# PIZ-Dual_v886.net
KiCad netlist of a schematic drawn in EAGLE
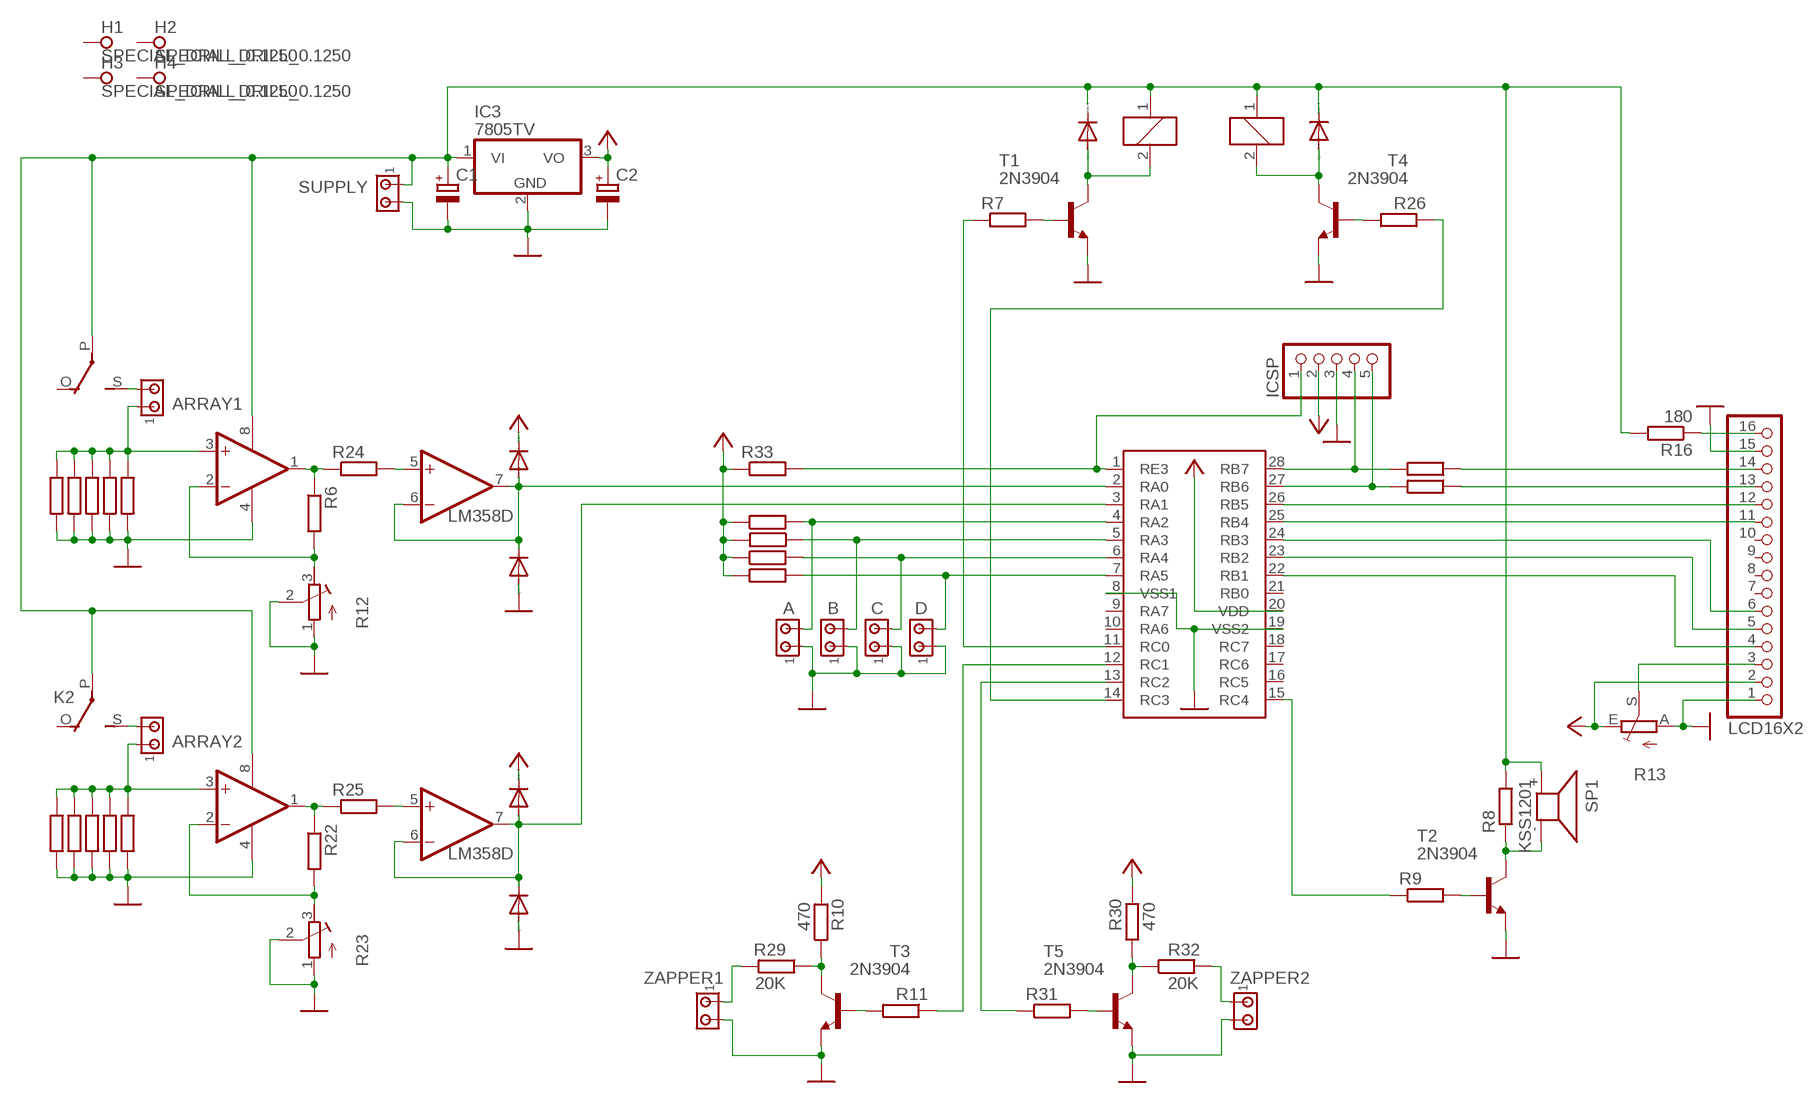
[diagram p0: schematic, sheet 1]

(export (version "E")
  (design (tool "Eeschema 10.0.6"))
  (components
    (comp (ref "A")
      (value "MTA02-100")
      (footprint "eagle-import:10X02MTA")
      (libsource (lib "eagle-import") (part "MTA02-100"))
    )
    (comp (ref "ARRAY1")
      (value "MTA02-100")
      (footprint "eagle-import:10X02MTA")
      (libsource (lib "eagle-import") (part "MTA02-100"))
    )
    (comp (ref "ARRAY2")
      (value "MTA02-100")
      (footprint "eagle-import:10X02MTA")
      (libsource (lib "eagle-import") (part "MTA02-100"))
    )
    (comp (ref "B")
      (value "MTA02-100")
      (footprint "eagle-import:10X02MTA")
      (libsource (lib "eagle-import") (part "MTA02-100"))
    )
    (comp (ref "C")
      (value "MTA02-100")
      (footprint "eagle-import:10X02MTA")
      (libsource (lib "eagle-import") (part "MTA02-100"))
    )
    (comp (ref "C1")
      (value "CPOL-EUE2.5-7")
      (footprint "eagle-import:E2,5-7")
      (libsource (lib "eagle-import") (part "CPOL-EUE2.5-7"))
    )
    (comp (ref "C2")
      (value "CPOL-EUE2.5-7")
      (footprint "eagle-import:E2,5-7")
      (libsource (lib "eagle-import") (part "CPOL-EUE2.5-7"))
    )
    (comp (ref "D")
      (value "MTA02-100")
      (footprint "eagle-import:10X02MTA")
      (libsource (lib "eagle-import") (part "MTA02-100"))
    )
    (comp (ref "D1")
      (value "1N4148DO35-7")
      (footprint "eagle-import:DO35-7")
      (libsource (lib "eagle-import") (part "1N4148DO35-7"))
    )
    (comp (ref "D2")
      (value "1N4148DO35-7")
      (footprint "eagle-import:DO35-7")
      (libsource (lib "eagle-import") (part "1N4148DO35-7"))
    )
    (comp (ref "D3")
      (value "1N4148DO35-7")
      (footprint "eagle-import:DO35-7")
      (libsource (lib "eagle-import") (part "1N4148DO35-7"))
    )
    (comp (ref "D4")
      (value "1N4148DO35-7")
      (footprint "eagle-import:DO35-7")
      (libsource (lib "eagle-import") (part "1N4148DO35-7"))
    )
    (comp (ref "D5")
      (value "1N4148DO35-7")
      (footprint "eagle-import:DO35-7")
      (libsource (lib "eagle-import") (part "1N4148DO35-7"))
    )
    (comp (ref "D6")
      (value "1N4148DO35-7")
      (footprint "eagle-import:DO35-7")
      (libsource (lib "eagle-import") (part "1N4148DO35-7"))
    )
    (comp (ref "H1")
      (value "SPECIAL_DRILL_0.1250")
      (footprint "eagle-import:PAD_0.1250")
      (libsource (lib "eagle-import") (part "SPECIAL_DRILL_0.1250"))
    )
    (comp (ref "H2")
      (value "SPECIAL_DRILL_0.1250")
      (footprint "eagle-import:PAD_0.1250")
      (libsource (lib "eagle-import") (part "SPECIAL_DRILL_0.1250"))
    )
    (comp (ref "H3")
      (value "SPECIAL_DRILL_0.1250")
      (footprint "eagle-import:PAD_0.1250")
      (libsource (lib "eagle-import") (part "SPECIAL_DRILL_0.1250"))
    )
    (comp (ref "H4")
      (value "SPECIAL_DRILL_0.1250")
      (footprint "eagle-import:PAD_0.1250")
      (libsource (lib "eagle-import") (part "SPECIAL_DRILL_0.1250"))
    )
    (comp (ref "IC2")
      (value "LM358D")
      (footprint "eagle-import:SO08")
      (libsource (lib "eagle-import") (part "LM358D"))
    )
    (comp (ref "IC3")
      (value "7805TV")
      (footprint "eagle-import:TO220V")
      (libsource (lib "eagle-import") (part "78TV05"))
    )
    (comp (ref "IC4")
      (value "LM358D")
      (footprint "eagle-import:SO08")
      (libsource (lib "eagle-import") (part "LM358D"))
    )
    (comp (ref "ICSP")
      (value "PINHD-1X55X2MM")
      (footprint "eagle-import:1_05X2MM")
      (libsource (lib "eagle-import") (part "PINHD-1X55X2MM"))
    )
    (comp (ref "K1")
      (value "G5L")
      (footprint "eagle-import:G5LE")
      (libsource (lib "eagle-import") (part "G5L"))
    )
    (comp (ref "K2")
      (value "G5L")
      (footprint "eagle-import:G5LE")
      (libsource (lib "eagle-import") (part "G5L"))
    )
    (comp (ref "LCD16X2")
      (value "PINHD-1X16")
      (footprint "eagle-import:1X16")
      (libsource (lib "eagle-import") (part "PINHD-1X16"))
    )
    (comp (ref "R1")
      (value "R-EU_R1210")
      (footprint "eagle-import:R1210")
      (libsource (lib "eagle-import") (part "R-EU_R1210"))
    )
    (comp (ref "R2")
      (value "R-EU_R1210")
      (footprint "eagle-import:R1210")
      (libsource (lib "eagle-import") (part "R-EU_R1210"))
    )
    (comp (ref "R3")
      (value "R-EU_R1210")
      (footprint "eagle-import:R1210")
      (libsource (lib "eagle-import") (part "R-EU_R1210"))
    )
    (comp (ref "R4")
      (value "R-EU_R1210")
      (footprint "eagle-import:R1210")
      (libsource (lib "eagle-import") (part "R-EU_R1210"))
    )
    (comp (ref "R5")
      (value "R-EU_R1210")
      (footprint "eagle-import:R1210")
      (libsource (lib "eagle-import") (part "R-EU_R1210"))
    )
    (comp (ref "R6")
      (value "R-EU_R1206")
      (footprint "eagle-import:R1206")
      (libsource (lib "eagle-import") (part "R-EU_R1206"))
    )
    (comp (ref "R7")
      (value "R-EU_R1206")
      (footprint "eagle-import:R1206")
      (libsource (lib "eagle-import") (part "R-EU_R1206"))
    )
    (comp (ref "R8")
      (value "R-EU_R1210")
      (footprint "eagle-import:R1210")
      (libsource (lib "eagle-import") (part "R-EU_R1210"))
    )
    (comp (ref "R9")
      (value "R-EU_R1206")
      (footprint "eagle-import:R1206")
      (libsource (lib "eagle-import") (part "R-EU_R1206"))
    )
    (comp (ref "R10")
      (value "470")
      (footprint "eagle-import:R1206")
      (libsource (lib "eagle-import") (part "R-EU_R1206"))
    )
    (comp (ref "R11")
      (value "R-EU_R1206")
      (footprint "eagle-import:R1206")
      (libsource (lib "eagle-import") (part "R-EU_R1206"))
    )
    (comp (ref "R12")
      (value "R-TRIMM64W")
      (footprint "eagle-import:RTRIM64W")
      (libsource (lib "eagle-import") (part "R-TRIMM64W"))
    )
    (comp (ref "R13")
      (value "TRIM_EU-CA6V")
      (footprint "eagle-import:CA6V")
      (libsource (lib "eagle-import") (part "TRIM_EU-CA6V"))
    )
    (comp (ref "R14")
      (value "R-EU_R1206")
      (footprint "eagle-import:R1206")
      (libsource (lib "eagle-import") (part "R-EU_R1206"))
    )
    (comp (ref "R15")
      (value "R-EU_R1206")
      (footprint "eagle-import:R1206")
      (libsource (lib "eagle-import") (part "R-EU_R1206"))
    )
    (comp (ref "R16")
      (value "180")
      (footprint "eagle-import:R2512")
      (libsource (lib "eagle-import") (part "R-EU_R2512"))
    )
    (comp (ref "R17")
      (value "R-EU_R1210")
      (footprint "eagle-import:R1210")
      (libsource (lib "eagle-import") (part "R-EU_R1210"))
    )
    (comp (ref "R18")
      (value "R-EU_R1210")
      (footprint "eagle-import:R1210")
      (libsource (lib "eagle-import") (part "R-EU_R1210"))
    )
    (comp (ref "R19")
      (value "R-EU_R1210")
      (footprint "eagle-import:R1210")
      (libsource (lib "eagle-import") (part "R-EU_R1210"))
    )
    (comp (ref "R20")
      (value "R-EU_R1210")
      (footprint "eagle-import:R1210")
      (libsource (lib "eagle-import") (part "R-EU_R1210"))
    )
    (comp (ref "R21")
      (value "R-EU_R1210")
      (footprint "eagle-import:R1210")
      (libsource (lib "eagle-import") (part "R-EU_R1210"))
    )
    (comp (ref "R22")
      (value "R-EU_R1206")
      (footprint "eagle-import:R1206")
      (libsource (lib "eagle-import") (part "R-EU_R1206"))
    )
    (comp (ref "R23")
      (value "R-TRIMM64W")
      (footprint "eagle-import:RTRIM64W")
      (libsource (lib "eagle-import") (part "R-TRIMM64W"))
    )
    (comp (ref "R24")
      (value "R-EU_R1206")
      (footprint "eagle-import:R1206")
      (libsource (lib "eagle-import") (part "R-EU_R1206"))
    )
    (comp (ref "R25")
      (value "R-EU_R1206")
      (footprint "eagle-import:R1206")
      (libsource (lib "eagle-import") (part "R-EU_R1206"))
    )
    (comp (ref "R26")
      (value "R-EU_R1206")
      (footprint "eagle-import:R1206")
      (libsource (lib "eagle-import") (part "R-EU_R1206"))
    )
    (comp (ref "R27")
      (value "R-EU_R1206")
      (footprint "eagle-import:R1206")
      (libsource (lib "eagle-import") (part "R-EU_R1206"))
    )
    (comp (ref "R28")
      (value "R-EU_R1206")
      (footprint "eagle-import:R1206")
      (libsource (lib "eagle-import") (part "R-EU_R1206"))
    )
    (comp (ref "R29")
      (value "20K")
      (footprint "eagle-import:R1206")
      (libsource (lib "eagle-import") (part "R-EU_R1206"))
    )
    (comp (ref "R30")
      (value "470")
      (footprint "eagle-import:R1206")
      (libsource (lib "eagle-import") (part "R-EU_R1206"))
    )
    (comp (ref "R31")
      (value "R-EU_R1206")
      (footprint "eagle-import:R1206")
      (libsource (lib "eagle-import") (part "R-EU_R1206"))
    )
    (comp (ref "R32")
      (value "20K")
      (footprint "eagle-import:R1206")
      (libsource (lib "eagle-import") (part "R-EU_R1206"))
    )
    (comp (ref "R33")
      (value "R-EU_R1206")
      (footprint "eagle-import:R1206")
      (libsource (lib "eagle-import") (part "R-EU_R1206"))
    )
    (comp (ref "R34")
      (value "R-EU_R1206")
      (footprint "eagle-import:R1206")
      (libsource (lib "eagle-import") (part "R-EU_R1206"))
    )
    (comp (ref "R35")
      (value "R-EU_R1206")
      (footprint "eagle-import:R1206")
      (libsource (lib "eagle-import") (part "R-EU_R1206"))
    )
    (comp (ref "SP1")
      (value "KSS1201")
      (footprint "eagle-import:KSS1201")
      (libsource (lib "eagle-import") (part "KSS1201"))
    )
    (comp (ref "SUPPLY")
      (value "MTA02-100")
      (footprint "eagle-import:10X02MTA")
      (libsource (lib "eagle-import") (part "MTA02-100"))
    )
    (comp (ref "T1")
      (value "2N3904")
      (footprint "eagle-import:TO92")
      (libsource (lib "eagle-import") (part "2N3904"))
    )
    (comp (ref "T2")
      (value "2N3904")
      (footprint "eagle-import:TO92")
      (libsource (lib "eagle-import") (part "2N3904"))
    )
    (comp (ref "T3")
      (value "2N3904")
      (footprint "eagle-import:TO92")
      (libsource (lib "eagle-import") (part "2N3904"))
    )
    (comp (ref "T4")
      (value "2N3904")
      (footprint "eagle-import:TO92")
      (libsource (lib "eagle-import") (part "2N3904"))
    )
    (comp (ref "T5")
      (value "2N3904")
      (footprint "eagle-import:TO92")
      (libsource (lib "eagle-import") (part "2N3904"))
    )
    (comp (ref "U$1")
      (value "PIC16F88")
      (footprint "eagle-import:SO28W")
      (libsource (lib "eagle-import") (part "PIC16F88"))
    )
    (comp (ref "ZAPPER1")
      (value "MTA02-100")
      (footprint "eagle-import:10X02MTA")
      (libsource (lib "eagle-import") (part "MTA02-100"))
    )
    (comp (ref "ZAPPER2")
      (value "MTA02-100")
      (footprint "eagle-import:10X02MTA")
      (libsource (lib "eagle-import") (part "MTA02-100"))
    )
  )
  (nets
    (net (code "1") (name "GND") (class "Default")
      (node (ref "A") (pin "1") (pinfunction "1_1") (pintype "passive"))
      (node (ref "B") (pin "1") (pinfunction "1_1") (pintype "passive"))
      (node (ref "C") (pin "1") (pinfunction "1_1") (pintype "passive"))
      (node (ref "C1") (pin "-") (pinfunction "-_-") (pintype "passive"))
      (node (ref "C2") (pin "-") (pinfunction "-_-") (pintype "passive"))
      (node (ref "D") (pin "1") (pinfunction "1_1") (pintype "passive"))
      (node (ref "D2") (pin "A") (pinfunction "A_A") (pintype "passive"))
      (node (ref "D5") (pin "A") (pinfunction "A_A") (pintype "passive"))
      (node (ref "IC2") (pin "4") (pinfunction "V-_4") (pintype "power_in"))
      (node (ref "IC3") (pin "2") (pinfunction "GND_2") (pintype "passive"))
      (node (ref "IC4") (pin "4") (pinfunction "V-_4") (pintype "power_in"))
      (node (ref "ICSP") (pin "3") (pinfunction "3_3") (pintype "passive"))
      (node (ref "LCD16X2") (pin "1") (pinfunction "1_1") (pintype "passive"))
      (node (ref "LCD16X2") (pin "15") (pinfunction "15_15") (pintype "passive"))
      (node (ref "R1") (pin "2") (pinfunction "2_2") (pintype "passive"))
      (node (ref "R12") (pin "1") (pinfunction "A_1") (pintype "passive"))
      (node (ref "R12") (pin "2") (pinfunction "S_2") (pintype "passive"))
      (node (ref "R13") (pin "A") (pinfunction "A_A") (pintype "passive"))
      (node (ref "R17") (pin "2") (pinfunction "2_2") (pintype "passive"))
      (node (ref "R18") (pin "2") (pinfunction "2_2") (pintype "passive"))
      (node (ref "R19") (pin "2") (pinfunction "2_2") (pintype "passive"))
      (node (ref "R2") (pin "2") (pinfunction "2_2") (pintype "passive"))
      (node (ref "R20") (pin "2") (pinfunction "2_2") (pintype "passive"))
      (node (ref "R21") (pin "2") (pinfunction "2_2") (pintype "passive"))
      (node (ref "R23") (pin "1") (pinfunction "A_1") (pintype "passive"))
      (node (ref "R23") (pin "2") (pinfunction "S_2") (pintype "passive"))
      (node (ref "R3") (pin "2") (pinfunction "2_2") (pintype "passive"))
      (node (ref "R4") (pin "2") (pinfunction "2_2") (pintype "passive"))
      (node (ref "R5") (pin "2") (pinfunction "2_2") (pintype "passive"))
      (node (ref "SUPPLY") (pin "2") (pinfunction "2_2") (pintype "passive"))
      (node (ref "T1") (pin "3") (pinfunction "E_3") (pintype "passive"))
      (node (ref "T2") (pin "3") (pinfunction "E_3") (pintype "passive"))
      (node (ref "T3") (pin "3") (pinfunction "E_3") (pintype "passive"))
      (node (ref "T4") (pin "3") (pinfunction "E_3") (pintype "passive"))
      (node (ref "T5") (pin "3") (pinfunction "E_3") (pintype "passive"))
      (node (ref "U$1") (pin "19") (pinfunction "VSS2_19") (pintype "power_in"))
      (node (ref "U$1") (pin "8") (pinfunction "VSS1_8") (pintype "power_in"))
      (node (ref "ZAPPER1") (pin "2") (pinfunction "2_2") (pintype "passive"))
      (node (ref "ZAPPER2") (pin "2") (pinfunction "2_2") (pintype "passive"))
    )
    (net (code "2") (name "Net-(ARRAY1-Pad2)") (class "Default")
      (node (ref "ARRAY1") (pin "2") (pinfunction "2_2") (pintype "passive"))
      (node (ref "K1") (pin "S") (pinfunction "S_S") (pintype "passive"))
    )
    (net (code "3") (name "Net-(ARRAY2-Pad2)") (class "Default")
      (node (ref "ARRAY2") (pin "2") (pinfunction "2_2") (pintype "passive"))
      (node (ref "K2") (pin "S") (pinfunction "S_S") (pintype "passive"))
    )
    (net (code "4") (name "Net-(IC2A-+IN)") (class "Default")
      (node (ref "ARRAY1") (pin "1") (pinfunction "1_1") (pintype "passive"))
      (node (ref "IC2") (pin "3") (pinfunction "+IN_3") (pintype "input"))
      (node (ref "R1") (pin "1") (pinfunction "1_1") (pintype "passive"))
      (node (ref "R2") (pin "1") (pinfunction "1_1") (pintype "passive"))
      (node (ref "R3") (pin "1") (pinfunction "1_1") (pintype "passive"))
      (node (ref "R4") (pin "1") (pinfunction "1_1") (pintype "passive"))
      (node (ref "R5") (pin "1") (pinfunction "1_1") (pintype "passive"))
    )
    (net (code "5") (name "Net-(IC2A--IN)") (class "Default")
      (node (ref "IC2") (pin "2") (pinfunction "-IN_2") (pintype "input"))
      (node (ref "R12") (pin "3") (pinfunction "E_3") (pintype "passive"))
      (node (ref "R6") (pin "2") (pinfunction "2_2") (pintype "passive"))
    )
    (net (code "6") (name "Net-(IC2A-OUT)") (class "Default")
      (node (ref "IC2") (pin "1") (pinfunction "OUT_1") (pintype "output"))
      (node (ref "R24") (pin "1") (pinfunction "1_1") (pintype "passive"))
      (node (ref "R6") (pin "1") (pinfunction "1_1") (pintype "passive"))
    )
    (net (code "7") (name "Net-(IC2B-+IN)") (class "Default")
      (node (ref "IC2") (pin "5") (pinfunction "+IN_5") (pintype "input"))
      (node (ref "R24") (pin "2") (pinfunction "2_2") (pintype "passive"))
    )
    (net (code "8") (name "Net-(IC2B--IN)") (class "Default")
      (node (ref "D1") (pin "A") (pinfunction "A_A") (pintype "passive"))
      (node (ref "D2") (pin "C") (pinfunction "C_C") (pintype "passive"))
      (node (ref "IC2") (pin "6") (pinfunction "-IN_6") (pintype "input"))
      (node (ref "IC2") (pin "7") (pinfunction "OUT_7") (pintype "output"))
      (node (ref "U$1") (pin "2") (pinfunction "RA0_2") (pintype "bidirectional"))
    )
    (net (code "9") (name "Net-(IC2C-V+)") (class "Default")
      (node (ref "C1") (pin "+") (pinfunction "+_+") (pintype "passive"))
      (node (ref "D6") (pin "C") (pinfunction "C_C") (pintype "passive"))
      (node (ref "IC2") (pin "8") (pinfunction "V+_8") (pintype "power_in"))
      (node (ref "IC3") (pin "1") (pinfunction "VI_1") (pintype "input"))
      (node (ref "IC4") (pin "8") (pinfunction "V+_8") (pintype "power_in"))
      (node (ref "K1") (pin "1") (pinfunction "1_1") (pintype "passive"))
      (node (ref "K1") (pin "P") (pinfunction "P_P") (pintype "passive"))
      (node (ref "K2") (pin "1") (pinfunction "1_1") (pintype "passive"))
      (node (ref "K2") (pin "P") (pinfunction "P_P") (pintype "passive"))
      (node (ref "R16") (pin "2") (pinfunction "2_2") (pintype "passive"))
      (node (ref "R8") (pin "2") (pinfunction "2_2") (pintype "passive"))
      (node (ref "SP1") (pin "+") (pinfunction "1_+") (pintype "passive"))
      (node (ref "SUPPLY") (pin "1") (pinfunction "1_1") (pintype "passive"))
    )
    (net (code "10") (name "Net-(IC4A-+IN)") (class "Default")
      (node (ref "ARRAY2") (pin "1") (pinfunction "1_1") (pintype "passive"))
      (node (ref "IC4") (pin "3") (pinfunction "+IN_3") (pintype "input"))
      (node (ref "R17") (pin "1") (pinfunction "1_1") (pintype "passive"))
      (node (ref "R18") (pin "1") (pinfunction "1_1") (pintype "passive"))
      (node (ref "R19") (pin "1") (pinfunction "1_1") (pintype "passive"))
      (node (ref "R20") (pin "1") (pinfunction "1_1") (pintype "passive"))
      (node (ref "R21") (pin "1") (pinfunction "1_1") (pintype "passive"))
    )
    (net (code "11") (name "Net-(IC4A--IN)") (class "Default")
      (node (ref "IC4") (pin "2") (pinfunction "-IN_2") (pintype "input"))
      (node (ref "R22") (pin "2") (pinfunction "2_2") (pintype "passive"))
      (node (ref "R23") (pin "3") (pinfunction "E_3") (pintype "passive"))
    )
    (net (code "12") (name "Net-(IC4A-OUT)") (class "Default")
      (node (ref "IC4") (pin "1") (pinfunction "OUT_1") (pintype "output"))
      (node (ref "R22") (pin "1") (pinfunction "1_1") (pintype "passive"))
      (node (ref "R25") (pin "1") (pinfunction "1_1") (pintype "passive"))
    )
    (net (code "13") (name "Net-(IC4B-+IN)") (class "Default")
      (node (ref "IC4") (pin "5") (pinfunction "+IN_5") (pintype "input"))
      (node (ref "R25") (pin "2") (pinfunction "2_2") (pintype "passive"))
    )
    (net (code "14") (name "Net-(IC4B--IN)") (class "Default")
      (node (ref "D4") (pin "A") (pinfunction "A_A") (pintype "passive"))
      (node (ref "D5") (pin "C") (pinfunction "C_C") (pintype "passive"))
      (node (ref "IC4") (pin "6") (pinfunction "-IN_6") (pintype "input"))
      (node (ref "IC4") (pin "7") (pinfunction "OUT_7") (pintype "output"))
      (node (ref "U$1") (pin "3") (pinfunction "RA1_3") (pintype "bidirectional"))
    )
    (net (code "15") (name "Net-(LCD16X2-Pad3)") (class "Default")
      (node (ref "LCD16X2") (pin "3") (pinfunction "3_3") (pintype "passive"))
      (node (ref "R13") (pin "S") (pinfunction "S_S") (pintype "passive"))
    )
    (net (code "16") (name "Net-(LCD16X2-Pad13)") (class "Default")
      (node (ref "LCD16X2") (pin "13") (pinfunction "13_13") (pintype "passive"))
      (node (ref "R28") (pin "1") (pinfunction "1_1") (pintype "passive"))
    )
    (net (code "17") (name "Net-(LCD16X2-Pad14)") (class "Default")
      (node (ref "LCD16X2") (pin "14") (pinfunction "14_14") (pintype "passive"))
      (node (ref "R27") (pin "1") (pinfunction "1_1") (pintype "passive"))
    )
    (net (code "18") (name "Net-(LCD16X2-Pad16)") (class "Default")
      (node (ref "LCD16X2") (pin "16") (pinfunction "16_16") (pintype "passive"))
      (node (ref "R16") (pin "1") (pinfunction "1_1") (pintype "passive"))
    )
    (net (code "19") (name "Net-(R29-Pad2)") (class "Default")
      (node (ref "R29") (pin "2") (pinfunction "2_2") (pintype "passive"))
      (node (ref "ZAPPER1") (pin "1") (pinfunction "1_1") (pintype "passive"))
    )
    (net (code "20") (name "Net-(R32-Pad2)") (class "Default")
      (node (ref "R32") (pin "2") (pinfunction "2_2") (pintype "passive"))
      (node (ref "ZAPPER2") (pin "1") (pinfunction "1_1") (pintype "passive"))
    )
    (net (code "21") (name "Net-(SP1-2)") (class "Default")
      (node (ref "R8") (pin "1") (pinfunction "1_1") (pintype "passive"))
      (node (ref "SP1") (pin "-") (pinfunction "2_-") (pintype "passive"))
      (node (ref "T2") (pin "1") (pinfunction "C_1") (pintype "passive"))
    )
    (net (code "22") (name "Net-(T1-B)") (class "Default")
      (node (ref "R7") (pin "2") (pinfunction "2_2") (pintype "passive"))
      (node (ref "T1") (pin "2") (pinfunction "B_2") (pintype "passive"))
    )
    (net (code "23") (name "Net-(T1-C)") (class "Default")
      (node (ref "D3") (pin "A") (pinfunction "A_A") (pintype "passive"))
      (node (ref "K1") (pin "2") (pinfunction "2_2") (pintype "passive"))
      (node (ref "T1") (pin "1") (pinfunction "C_1") (pintype "passive"))
    )
    (net (code "24") (name "Net-(T2-B)") (class "Default")
      (node (ref "R9") (pin "2") (pinfunction "2_2") (pintype "passive"))
      (node (ref "T2") (pin "2") (pinfunction "B_2") (pintype "passive"))
    )
    (net (code "25") (name "Net-(T3-B)") (class "Default")
      (node (ref "R11") (pin "2") (pinfunction "2_2") (pintype "passive"))
      (node (ref "T3") (pin "2") (pinfunction "B_2") (pintype "passive"))
    )
    (net (code "26") (name "Net-(T3-C)") (class "Default")
      (node (ref "R10") (pin "1") (pinfunction "1_1") (pintype "passive"))
      (node (ref "R29") (pin "1") (pinfunction "1_1") (pintype "passive"))
      (node (ref "T3") (pin "1") (pinfunction "C_1") (pintype "passive"))
    )
    (net (code "27") (name "Net-(T4-B)") (class "Default")
      (node (ref "R26") (pin "2") (pinfunction "2_2") (pintype "passive"))
      (node (ref "T4") (pin "2") (pinfunction "B_2") (pintype "passive"))
    )
    (net (code "28") (name "Net-(T4-C)") (class "Default")
      (node (ref "D6") (pin "A") (pinfunction "A_A") (pintype "passive"))
      (node (ref "K2") (pin "2") (pinfunction "2_2") (pintype "passive"))
      (node (ref "T4") (pin "1") (pinfunction "C_1") (pintype "passive"))
    )
    (net (code "29") (name "Net-(T5-B)") (class "Default")
      (node (ref "R31") (pin "2") (pinfunction "2_2") (pintype "passive"))
      (node (ref "T5") (pin "2") (pinfunction "B_2") (pintype "passive"))
    )
    (net (code "30") (name "Net-(T5-C)") (class "Default")
      (node (ref "R30") (pin "1") (pinfunction "1_1") (pintype "passive"))
      (node (ref "R32") (pin "1") (pinfunction "1_1") (pintype "passive"))
      (node (ref "T5") (pin "1") (pinfunction "C_1") (pintype "passive"))
    )
    (net (code "31") (name "Net-(U$1-RA2)") (class "Default")
      (node (ref "A") (pin "2") (pinfunction "2_2") (pintype "passive"))
      (node (ref "R15") (pin "2") (pinfunction "2_2") (pintype "passive"))
      (node (ref "U$1") (pin "4") (pinfunction "RA2_4") (pintype "bidirectional"))
    )
    (net (code "32") (name "Net-(U$1-RA3)") (class "Default")
      (node (ref "B") (pin "2") (pinfunction "2_2") (pintype "passive"))
      (node (ref "R14") (pin "1") (pinfunction "1_1") (pintype "passive"))
      (node (ref "U$1") (pin "5") (pinfunction "RA3_5") (pintype "bidirectional"))
    )
    (net (code "33") (name "Net-(U$1-RA4)") (class "Default")
      (node (ref "C") (pin "2") (pinfunction "2_2") (pintype "passive"))
      (node (ref "R34") (pin "2") (pinfunction "2_2") (pintype "passive"))
      (node (ref "U$1") (pin "6") (pinfunction "RA4_6") (pintype "bidirectional"))
    )
    (net (code "34") (name "Net-(U$1-RA5)") (class "Default")
      (node (ref "D") (pin "2") (pinfunction "2_2") (pintype "passive"))
      (node (ref "R35") (pin "2") (pinfunction "2_2") (pintype "passive"))
      (node (ref "U$1") (pin "7") (pinfunction "RA5_7") (pintype "bidirectional"))
    )
    (net (code "35") (name "Net-(U$1-RB1)") (class "Default")
      (node (ref "LCD16X2") (pin "4") (pinfunction "4_4") (pintype "passive"))
      (node (ref "U$1") (pin "22") (pinfunction "RB1_22") (pintype "bidirectional"))
    )
    (net (code "36") (name "Net-(U$1-RB2)") (class "Default")
      (node (ref "LCD16X2") (pin "5") (pinfunction "5_5") (pintype "passive"))
      (node (ref "U$1") (pin "23") (pinfunction "RB2_23") (pintype "bidirectional"))
    )
    (net (code "37") (name "Net-(U$1-RB3)") (class "Default")
      (node (ref "LCD16X2") (pin "6") (pinfunction "6_6") (pintype "passive"))
      (node (ref "U$1") (pin "24") (pinfunction "RB3_24") (pintype "bidirectional"))
    )
    (net (code "38") (name "Net-(U$1-RB4)") (class "Default")
      (node (ref "LCD16X2") (pin "11") (pinfunction "11_11") (pintype "passive"))
      (node (ref "U$1") (pin "25") (pinfunction "RB4_25") (pintype "bidirectional"))
    )
    (net (code "39") (name "Net-(U$1-RB5)") (class "Default")
      (node (ref "LCD16X2") (pin "12") (pinfunction "12_12") (pintype "passive"))
      (node (ref "U$1") (pin "26") (pinfunction "RB5_26") (pintype "bidirectional"))
    )
    (net (code "40") (name "Net-(U$1-RB6)") (class "Default")
      (node (ref "ICSP") (pin "5") (pinfunction "5_5") (pintype "passive"))
      (node (ref "R28") (pin "2") (pinfunction "2_2") (pintype "passive"))
      (node (ref "U$1") (pin "27") (pinfunction "RB6_27") (pintype "bidirectional"))
    )
    (net (code "41") (name "Net-(U$1-RB7)") (class "Default")
      (node (ref "ICSP") (pin "4") (pinfunction "4_4") (pintype "passive"))
      (node (ref "R27") (pin "2") (pinfunction "2_2") (pintype "passive"))
      (node (ref "U$1") (pin "28") (pinfunction "RB7_28") (pintype "bidirectional"))
    )
    (net (code "42") (name "Net-(U$1-RC0)") (class "Default")
      (node (ref "R7") (pin "1") (pinfunction "1_1") (pintype "passive"))
      (node (ref "U$1") (pin "11") (pinfunction "RC0_11") (pintype "bidirectional"))
    )
    (net (code "43") (name "Net-(U$1-RC1)") (class "Default")
      (node (ref "R11") (pin "1") (pinfunction "1_1") (pintype "passive"))
      (node (ref "U$1") (pin "12") (pinfunction "RC1_12") (pintype "bidirectional"))
    )
    (net (code "44") (name "Net-(U$1-RC2)") (class "Default")
      (node (ref "R31") (pin "1") (pinfunction "1_1") (pintype "passive"))
      (node (ref "U$1") (pin "13") (pinfunction "RC2_13") (pintype "bidirectional"))
    )
    (net (code "45") (name "Net-(U$1-RC3)") (class "Default")
      (node (ref "R26") (pin "1") (pinfunction "1_1") (pintype "passive"))
      (node (ref "U$1") (pin "14") (pinfunction "RC3_14") (pintype "bidirectional"))
    )
    (net (code "46") (name "Net-(U$1-RC4)") (class "Default")
      (node (ref "R9") (pin "1") (pinfunction "1_1") (pintype "passive"))
      (node (ref "U$1") (pin "15") (pinfunction "RC4_15") (pintype "bidirectional"))
    )
    (net (code "47") (name "Net-(U$1-RE3)") (class "Default")
      (node (ref "ICSP") (pin "1") (pinfunction "1_1") (pintype "passive"))
      (node (ref "R33") (pin "2") (pinfunction "2_2") (pintype "passive"))
      (node (ref "U$1") (pin "1") (pinfunction "RE3_1") (pintype "bidirectional"))
    )
    (net (code "48") (name "VCC") (class "Default")
      (node (ref "C2") (pin "+") (pinfunction "+_+") (pintype "passive"))
      (node (ref "D1") (pin "C") (pinfunction "C_C") (pintype "passive"))
      (node (ref "D4") (pin "C") (pinfunction "C_C") (pintype "passive"))
      (node (ref "IC3") (pin "3") (pinfunction "VO_3") (pintype "passive"))
      (node (ref "ICSP") (pin "2") (pinfunction "2_2") (pintype "passive"))
      (node (ref "LCD16X2") (pin "2") (pinfunction "2_2") (pintype "passive"))
      (node (ref "R10") (pin "2") (pinfunction "2_2") (pintype "passive"))
      (node (ref "R13") (pin "E") (pinfunction "E_E") (pintype "passive"))
      (node (ref "R14") (pin "2") (pinfunction "2_2") (pintype "passive"))
      (node (ref "R15") (pin "1") (pinfunction "1_1") (pintype "passive"))
      (node (ref "R30") (pin "2") (pinfunction "2_2") (pintype "passive"))
      (node (ref "R33") (pin "1") (pinfunction "1_1") (pintype "passive"))
      (node (ref "R34") (pin "1") (pinfunction "1_1") (pintype "passive"))
      (node (ref "R35") (pin "1") (pinfunction "1_1") (pintype "passive"))
      (node (ref "U$1") (pin "20") (pinfunction "VDD_20") (pintype "power_in"))
    )
    (net (code "49") (name "unconnected-(D3-PadC)") (class "Default")
      (node (ref "D3") (pin "C") (pinfunction "C_C") (pintype "passive"))
    )
    (net (code "50") (name "unconnected-(H1-Pad1)") (class "Default")
      (node (ref "H1") (pin "1") (pinfunction "1_1") (pintype "passive"))
    )
    (net (code "51") (name "unconnected-(H2-Pad1)") (class "Default")
      (node (ref "H2") (pin "1") (pinfunction "1_1") (pintype "passive"))
    )
    (net (code "52") (name "unconnected-(H3-Pad1)") (class "Default")
      (node (ref "H3") (pin "1") (pinfunction "1_1") (pintype "passive"))
    )
    (net (code "53") (name "unconnected-(H4-Pad1)") (class "Default")
      (node (ref "H4") (pin "1") (pinfunction "1_1") (pintype "passive"))
    )
    (net (code "54") (name "unconnected-(K1-PadO)") (class "Default")
      (node (ref "K1") (pin "O") (pinfunction "O_O") (pintype "passive"))
    )
    (net (code "55") (name "unconnected-(K2-PadO)") (class "Default")
      (node (ref "K2") (pin "O") (pinfunction "O_O") (pintype "passive"))
    )
    (net (code "56") (name "unconnected-(LCD16X2-Pad7)") (class "Default")
      (node (ref "LCD16X2") (pin "7") (pinfunction "7_7") (pintype "passive"))
    )
    (net (code "57") (name "unconnected-(LCD16X2-Pad8)") (class "Default")
      (node (ref "LCD16X2") (pin "8") (pinfunction "8_8") (pintype "passive"))
    )
    (net (code "58") (name "unconnected-(LCD16X2-Pad9)") (class "Default")
      (node (ref "LCD16X2") (pin "9") (pinfunction "9_9") (pintype "passive"))
    )
    (net (code "59") (name "unconnected-(LCD16X2-Pad10)") (class "Default")
      (node (ref "LCD16X2") (pin "10") (pinfunction "10_10") (pintype "passive"))
    )
    (net (code "60") (name "unconnected-(U$1-RA6-Pad10)") (class "Default")
      (node (ref "U$1") (pin "10") (pinfunction "RA6_10") (pintype "bidirectional"))
    )
    (net (code "61") (name "unconnected-(U$1-RA7-Pad9)") (class "Default")
      (node (ref "U$1") (pin "9") (pinfunction "RA7_9") (pintype "bidirectional"))
    )
    (net (code "62") (name "unconnected-(U$1-RB0-Pad21)") (class "Default")
      (node (ref "U$1") (pin "21") (pinfunction "RB0_21") (pintype "bidirectional"))
    )
    (net (code "63") (name "unconnected-(U$1-RC5-Pad16)") (class "Default")
      (node (ref "U$1") (pin "16") (pinfunction "RC5_16") (pintype "bidirectional"))
    )
    (net (code "64") (name "unconnected-(U$1-RC6-Pad17)") (class "Default")
      (node (ref "U$1") (pin "17") (pinfunction "RC6_17") (pintype "bidirectional"))
    )
    (net (code "65") (name "unconnected-(U$1-RC7-Pad18)") (class "Default")
      (node (ref "U$1") (pin "18") (pinfunction "RC7_18") (pintype "bidirectional"))
    )
  )
)
